# H41R60.net
KiCad netlist of a schematic drawn in EAGLE
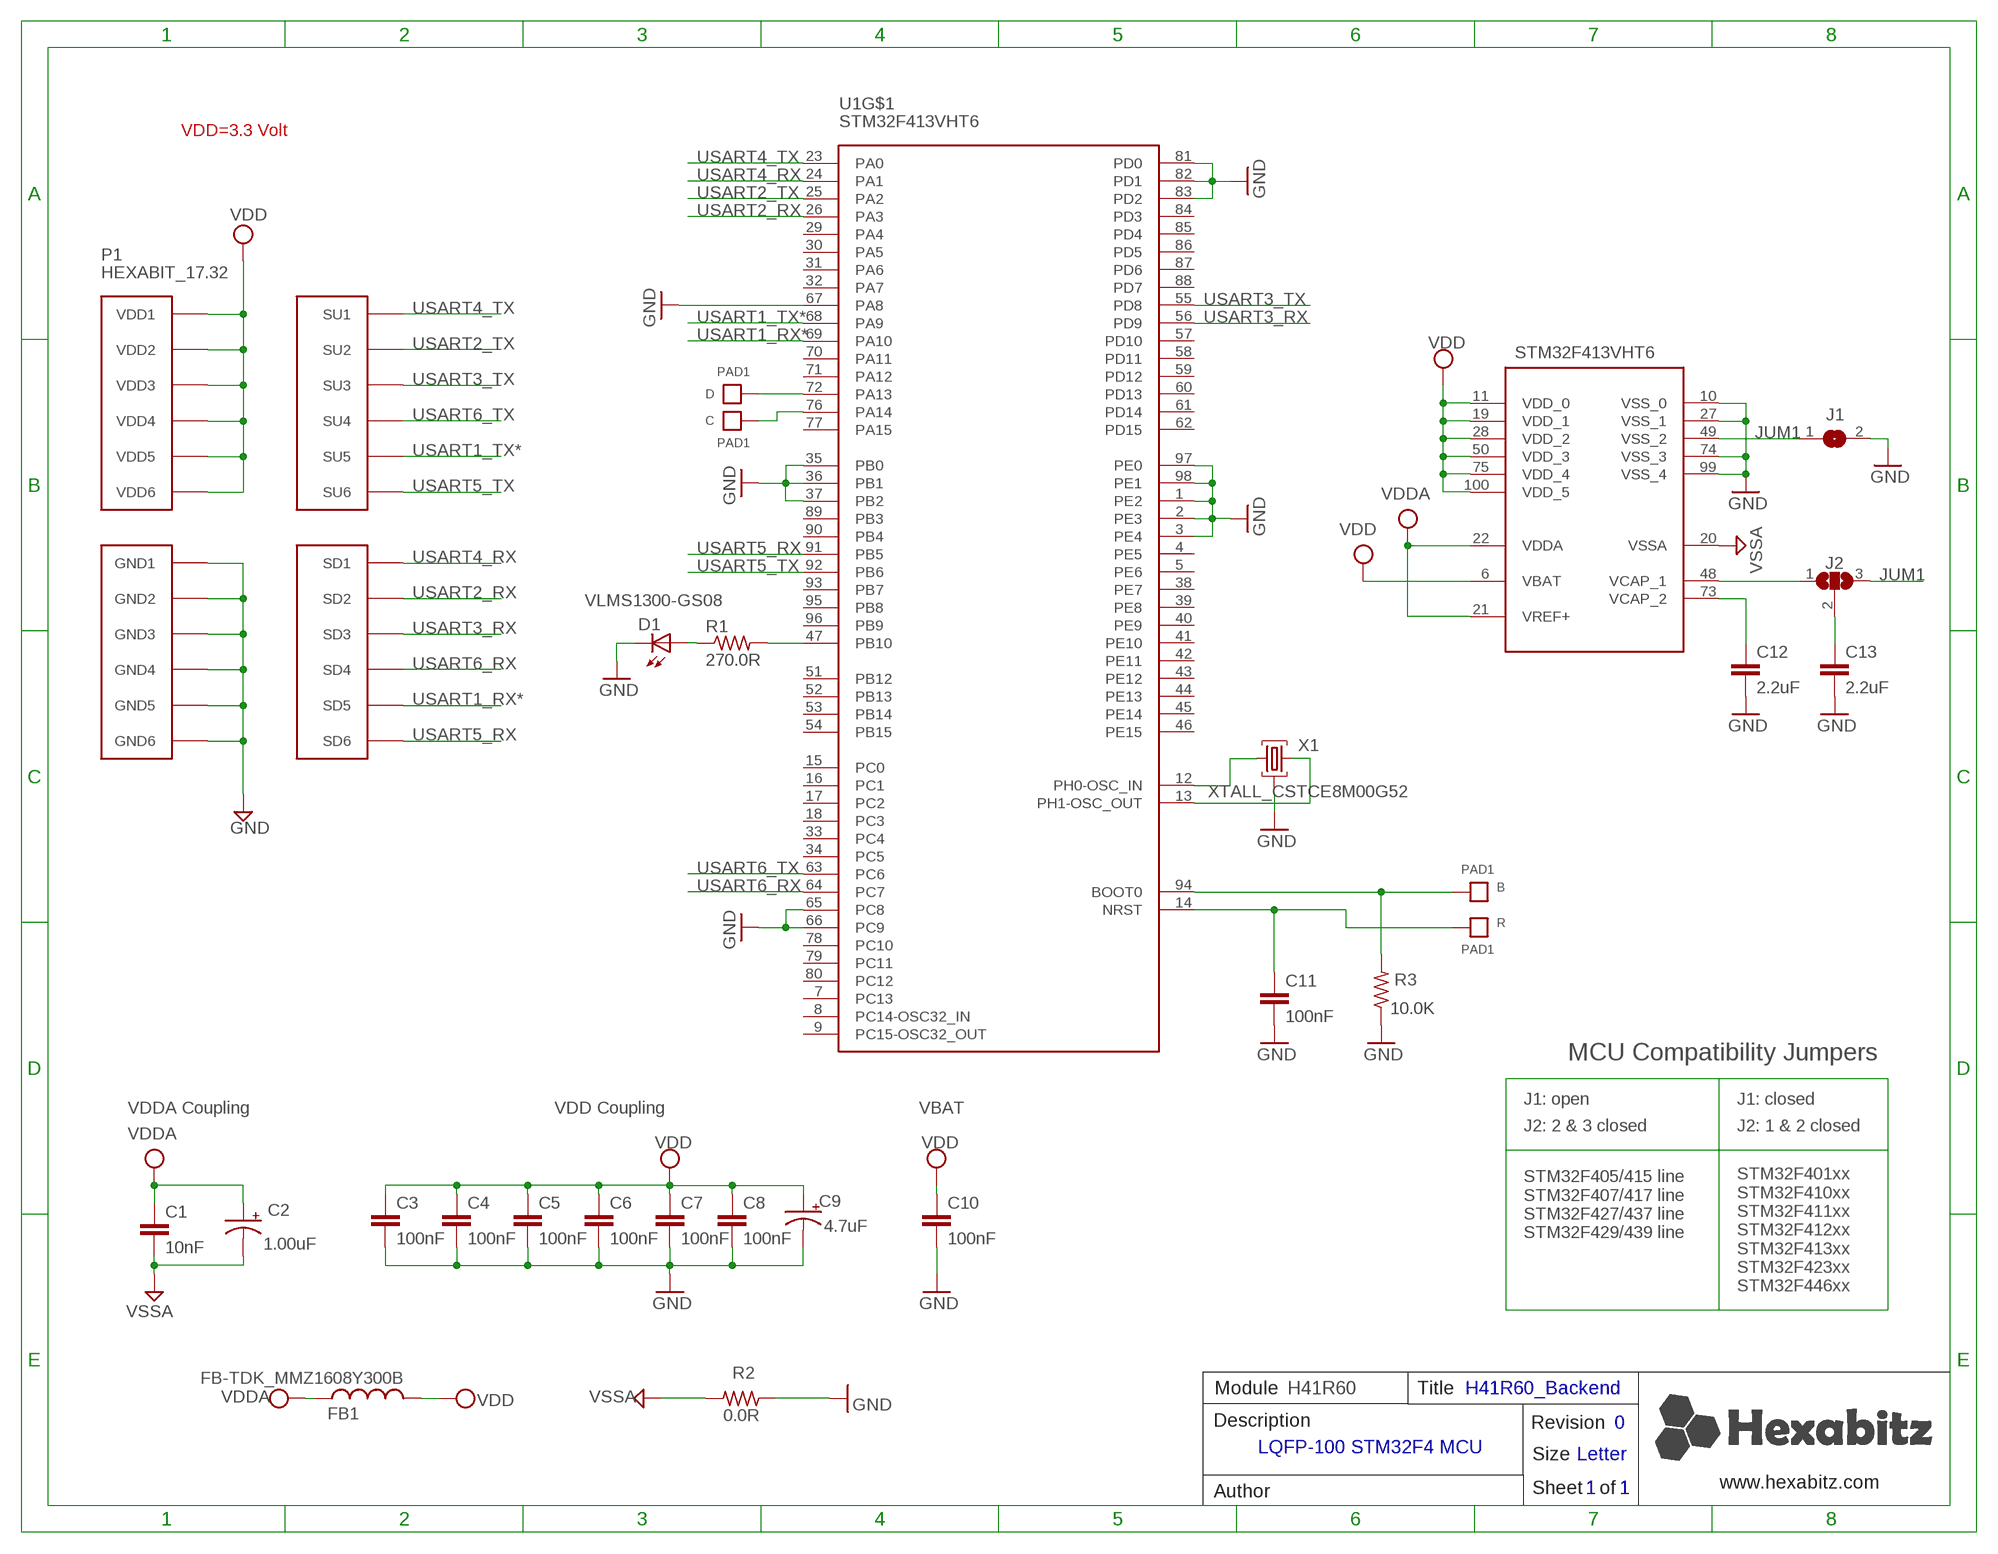
[diagram p0: schematic, sheet 1]

(export (version "E")
  (design (tool "Eeschema 10.0.6"))
  (components
    (comp (ref "B")
      (value "PAD1")
      (footprint "eagle-import:PAD1")
      (libsource (lib "eagle-import") (part "PAD1"))
    )
    (comp (ref "C")
      (value "PAD1")
      (footprint "eagle-import:PAD1")
      (libsource (lib "eagle-import") (part "PAD1"))
    )
    (comp (ref "C1")
      (value "10nF")
      (footprint "eagle-import:C-0603")
      (fields
        (field (name "CAPACITANCE") "10nF")
        (field (name "MFN") "KEMET")
        (field (name "MPN") "C0603C103K5RACTU")
        (field (name "OCTOPART_URL") "https://octopart.com/c0603c103k5ractu-kemet-133094?r=sp&s=R_iPBxLnSmGqhkU2rIMFpg")
        (field (name "TOLERANCE") "10%")
        (field (name "VOLTAGE_RATING") "50V")
      )
      (libsource (lib "eagle-import") (part "C-0603"))
    )
    (comp (ref "C2")
      (value "1.00uF")
      (footprint "eagle-import:C-0805-POL")
      (fields
        (field (name "CAPACITANCE") "1.00uF")
        (field (name "MFN") "Yageo")
        (field (name "MPN") "CC0805KKX7R7BB105")
        (field (name "OCTOPART_URL") "https://octopart.com/cc0805kkx7r7bb105-yageo-8376555?r=sp&s=YKl1wwtkROau_X5nniH2ig")
        (field (name "TOLERANCE") "10%")
        (field (name "VOLTAGE_RATING") "16V")
      )
      (libsource (lib "eagle-import") (part "C-0805-POL"))
    )
    (comp (ref "C3")
      (value "100nF")
      (footprint "eagle-import:C-0603")
      (fields
        (field (name "CAPACITANCE") "100nF")
        (field (name "MFN") "KEMET")
        (field (name "MPN") "C0603C104K8RACTU")
        (field (name "OCTOPART_URL") "https://octopart.com/c0603c104k8ractu-kemet-145075?r=sp&s=9bS9ASSwSEqMCE9KBEQZ0g")
        (field (name "TOLERANCE") "10%")
        (field (name "VOLTAGE_RATING") "10V")
      )
      (libsource (lib "eagle-import") (part "C-0603"))
    )
    (comp (ref "C4")
      (value "100nF")
      (footprint "eagle-import:C-0603")
      (fields
        (field (name "CAPACITANCE") "100nF")
        (field (name "MFN") "KEMET")
        (field (name "MPN") "C0603C104K8RACTU")
        (field (name "OCTOPART_URL") "https://octopart.com/c0603c104k8ractu-kemet-145075?r=sp&s=9bS9ASSwSEqMCE9KBEQZ0g")
        (field (name "TOLERANCE") "10%")
        (field (name "VOLTAGE_RATING") "10V")
      )
      (libsource (lib "eagle-import") (part "C-0603"))
    )
    (comp (ref "C5")
      (value "100nF")
      (footprint "eagle-import:C-0603")
      (fields
        (field (name "CAPACITANCE") "100nF")
        (field (name "MFN") "KEMET")
        (field (name "MPN") "C0603C104K8RACTU")
        (field (name "OCTOPART_URL") "https://octopart.com/c0603c104k8ractu-kemet-145075?r=sp&s=9bS9ASSwSEqMCE9KBEQZ0g")
        (field (name "TOLERANCE") "10%")
        (field (name "VOLTAGE_RATING") "10V")
      )
      (libsource (lib "eagle-import") (part "C-0603"))
    )
    (comp (ref "C6")
      (value "100nF")
      (footprint "eagle-import:C-0603")
      (fields
        (field (name "CAPACITANCE") "100nF")
        (field (name "MFN") "KEMET")
        (field (name "MPN") "C0603C104K8RACTU")
        (field (name "OCTOPART_URL") "https://octopart.com/c0603c104k8ractu-kemet-145075?r=sp&s=9bS9ASSwSEqMCE9KBEQZ0g")
        (field (name "TOLERANCE") "10%")
        (field (name "VOLTAGE_RATING") "10V")
      )
      (libsource (lib "eagle-import") (part "C-0603"))
    )
    (comp (ref "C7")
      (value "100nF")
      (footprint "eagle-import:C-0603")
      (fields
        (field (name "CAPACITANCE") "100nF")
        (field (name "MFN") "KEMET")
        (field (name "MPN") "C0603C104K8RACTU")
        (field (name "OCTOPART_URL") "https://octopart.com/c0603c104k8ractu-kemet-145075?r=sp&s=9bS9ASSwSEqMCE9KBEQZ0g")
        (field (name "TOLERANCE") "10%")
        (field (name "VOLTAGE_RATING") "10")
      )
      (libsource (lib "eagle-import") (part "C-0603"))
    )
    (comp (ref "C8")
      (value "100nF")
      (footprint "eagle-import:C-0603")
      (fields
        (field (name "CAPACITANCE") "100nF")
        (field (name "MFN") "KEMET")
        (field (name "MPN") "C0603C104K8RACTU")
        (field (name "OCTOPART_URL") "https://octopart.com/c0603c104k8ractu-kemet-145075?r=sp&s=9bS9ASSwSEqMCE9KBEQZ0g")
        (field (name "TOLERANCE") "10%")
        (field (name "VOLTAGE_RATING") "10V")
      )
      (libsource (lib "eagle-import") (part "C-0603"))
    )
    (comp (ref "C9")
      (value "4.7uF")
      (footprint "eagle-import:C-0805-POL")
      (fields
        (field (name "CAPACITANCE") "4.7uF")
        (field (name "MFN") "Murata")
        (field (name "MPN") "GRM21BC81E475KA12L")
        (field (name "OCTOPART_URL") "https://octopart.com/grm21bc81e475ka12l-murata-10331911?r=sp&s=RY3qZSD8T6mG6TC9CHI5qQ")
        (field (name "TOLERANCE") "10%")
        (field (name "VOLTAGE_RATING") "25V")
      )
      (libsource (lib "eagle-import") (part "C-0805-POL"))
    )
    (comp (ref "C10")
      (value "100nF")
      (footprint "eagle-import:C-0603")
      (fields
        (field (name "CAPACITANCE") "100nF")
        (field (name "MFN") "KEMET")
        (field (name "MPN") "C0603C104K8RACTU")
        (field (name "OCTOPART_URL") "https://octopart.com/c0603c104k8ractu-kemet-145075?r=sp&s=9bS9ASSwSEqMCE9KBEQZ0g")
        (field (name "TOLERANCE") "10V")
        (field (name "VOLTAGE_RATING") "10%")
      )
      (libsource (lib "eagle-import") (part "C-0603"))
    )
    (comp (ref "C11")
      (value "100nF")
      (footprint "eagle-import:C-0603")
      (fields
        (field (name "CAPACITANCE") "100nF")
        (field (name "MFN") "KEMET")
        (field (name "MPN") "C0603C104K8RACTU")
        (field (name "OCTOPART_URL") "https://octopart.com/c0603c104k8ractu-kemet-145075?r=sp&s=9bS9ASSwSEqMCE9KBEQZ0g")
        (field (name "TOLERANCE") "10%")
        (field (name "VOLTAGE_RATING") "10V")
      )
      (libsource (lib "eagle-import") (part "C-0603"))
    )
    (comp (ref "C12")
      (value "2.2uF")
      (footprint "eagle-import:C-0603")
      (fields
        (field (name "CAPACITANCE") "2.2uF")
        (field (name "MFN") "TDK Corporation")
        (field (name "MPN") "C1608X5R1C225K080AB")
        (field (name "OCTOPART_URL") "https://octopart.com/c1608x5r1c225k080ab-tdk-26013481?r=sp&s=zh0P7eqWSJSPxGSwstsLZg")
        (field (name "TOLERANCE") "16V")
        (field (name "VOLTAGE_RATING") "20%")
      )
      (libsource (lib "eagle-import") (part "C-0603"))
    )
    (comp (ref "C13")
      (value "2.2uF")
      (footprint "eagle-import:C-0603")
      (fields
        (field (name "CAPACITANCE") "2.2uF")
        (field (name "MFN") "TDK Corporation")
        (field (name "MPN") "C1608X5R1C225K080AB")
        (field (name "OCTOPART_URL") "https://octopart.com/c1608x5r1c225k080ab-tdk-26013481?r=sp&s=zh0P7eqWSJSPxGSwstsLZg")
        (field (name "TOLERANCE") "16V")
        (field (name "VOLTAGE_RATING") "20%")
      )
      (libsource (lib "eagle-import") (part "C-0603"))
    )
    (comp (ref "D")
      (value "PAD1")
      (footprint "eagle-import:PAD1")
      (libsource (lib "eagle-import") (part "PAD1"))
    )
    (comp (ref "D1")
      (value "VLMS1300-GS08")
      (footprint "eagle-import:VLMS1300-GS08")
      (fields
        (field (name "MFN") "Vishay")
        (field (name "MPN") "VLMS1300-GS08")
        (field (name "OCTOPART_URL") "https://octopart.com/vlms1300-gs08-vishay-21709201?r=sp&s=_gcP4_q8T1SC6PJQPTQ9yA")
      )
      (libsource (lib "eagle-import") (part "VLMS1300-GS08"))
    )
    (comp (ref "FB1")
      (value "FB-TDK_MMZ1608Y300B")
      (footprint "eagle-import:FB-TDK_MMZ1608Y300B")
      (fields
        (field (name "MFN") "TDK ")
        (field (name "MPN") "MMZ1608Y300B")
        (field (name "OCTOPART_URL") "https://octopart.com/mmz1608y300b-tdk-368280?r=sp&s=cd9_2ZEqQ9q9UNBuQgHAiA")
      )
      (libsource (lib "eagle-import") (part "FB-TDK_MMZ1608Y300B"))
    )
    (comp (ref "J1") (value "SJ") (footprint "eagle-import:SJ") (libsource (lib "eagle-import") (part "SJ")))
    (comp (ref "J2")
      (value "SJ2W")
      (footprint "eagle-import:SJ_2")
      (libsource (lib "eagle-import") (part "SJ2W"))
    )
    (comp (ref "P1")
      (value "HEXABIT_17.32")
      (footprint "eagle-import:HEXABIT_17.32")
      (libsource (lib "eagle-import") (part "HEXABIT_?17.32"))
    )
    (comp (ref "R")
      (value "PAD1")
      (footprint "eagle-import:PAD1")
      (libsource (lib "eagle-import") (part "PAD1"))
    )
    (comp (ref "R1")
      (value "270.0R")
      (footprint "eagle-import:R-0603")
      (fields
        (field (name "MFN") "Yageo")
        (field (name "MPN") "RC0603FR-07270RL")
        (field (name "OCTOPART_URL") "https://octopart.com/search?q=RC0603FR-07270RL&start=0")
        (field (name "RESISTANCE") "270.0 Ohm")
        (field (name "TOLERANCE") "1%")
      )
      (libsource (lib "eagle-import") (part "R-0603"))
    )
    (comp (ref "R2")
      (value "0.0R")
      (footprint "eagle-import:R-0603")
      (fields
        (field (name "MFN") "Yageo")
        (field (name "MPN") "RC0603JR-070RL")
        (field (name "OCTOPART_URL") "https://octopart.com/rc0603jr-070rl-yageo-1241539?r=sp&s=X2NteqRjRNWrnx42Y0aliA")
        (field (name "RESISTANCE") "0.0 Ohm")
      )
      (libsource (lib "eagle-import") (part "R-0603"))
    )
    (comp (ref "R3")
      (value "10.0K")
      (footprint "eagle-import:R-0603")
      (fields
        (field (name "MFN") "Yageo")
        (field (name "MPN") "RC0603JR-0710KL")
        (field (name "OCTOPART_URL") "https://octopart.com/search?q=RC0603JR-0710KL&start=0")
        (field (name "RESISTANCE") "10.0K Ohm")
        (field (name "TOLERANCE") "5%")
      )
      (libsource (lib "eagle-import") (part "R-0603"))
    )
    (comp (ref "U1")
      (value "STM32F413VHT6")
      (footprint "eagle-import:LQFP-100")
      (libsource (lib "eagle-import") (part "STM32F413VHT6"))
    )
    (comp (ref "X1")
      (value "XTALL_CSTCE8M00G52")
      (footprint "eagle-import:XTALL_CSTCE8M00G52")
      (fields (field (name "MPN") "CSTCE8M00G52Z-R0"))
      (libsource (lib "eagle-import") (part "XTALL_CSTCE8M00G52"))
    )
  )
  (nets
    (net (code "1") (name "/JUM1") (class "Default")
      (node (ref "J1") (pin "1") (pinfunction "1_1") (pintype "passive"))
      (node (ref "J2") (pin "3") (pinfunction "3_3") (pintype "passive"))
      (node (ref "U1") (pin "49") (pinfunction "VSS_2_49") (pintype "power_in"))
    )
    (net (code "3") (name "/USART1_RX*") (class "Default")
      (node (ref "P1") (pin "PAD_PD5") (pinfunction "SD5_PAD_PD5") (pintype "bidirectional"))
      (node (ref "U1") (pin "69") (pinfunction "PA10_69") (pintype "bidirectional"))
    )
    (net (code "4") (name "/USART1_TX*") (class "Default")
      (node (ref "P1") (pin "PAD_PU5") (pinfunction "SU5_PAD_PU5") (pintype "bidirectional"))
      (node (ref "U1") (pin "68") (pinfunction "PA9_68") (pintype "bidirectional"))
    )
    (net (code "5") (name "/USART2_RX") (class "Default")
      (node (ref "P1") (pin "PAD_PD2") (pinfunction "SD2_PAD_PD2") (pintype "bidirectional"))
      (node (ref "U1") (pin "26") (pinfunction "PA3_26") (pintype "bidirectional"))
    )
    (net (code "6") (name "/USART2_TX") (class "Default")
      (node (ref "P1") (pin "PAD_PU2") (pinfunction "SU2_PAD_PU2") (pintype "bidirectional"))
      (node (ref "U1") (pin "25") (pinfunction "PA2_25") (pintype "bidirectional"))
    )
    (net (code "7") (name "/USART3_RX") (class "Default")
      (node (ref "P1") (pin "PAD_PD3") (pinfunction "SD3_PAD_PD3") (pintype "bidirectional"))
      (node (ref "U1") (pin "56") (pinfunction "PD9_56") (pintype "bidirectional"))
    )
    (net (code "8") (name "/USART3_TX") (class "Default")
      (node (ref "P1") (pin "PAD_PU3") (pinfunction "SU3_PAD_PU3") (pintype "bidirectional"))
      (node (ref "U1") (pin "55") (pinfunction "PD8_55") (pintype "bidirectional"))
    )
    (net (code "9") (name "/USART4_RX") (class "Default")
      (node (ref "P1") (pin "PAD_PD1") (pinfunction "SD1_PAD_PD1") (pintype "bidirectional"))
      (node (ref "U1") (pin "24") (pinfunction "PA1_24") (pintype "bidirectional"))
    )
    (net (code "10") (name "/USART4_TX") (class "Default")
      (node (ref "P1") (pin "PAD_PU1") (pinfunction "SU1_PAD_PU1") (pintype "bidirectional"))
      (node (ref "U1") (pin "23") (pinfunction "PA0_23") (pintype "bidirectional"))
    )
    (net (code "11") (name "/USART5_RX") (class "Default")
      (node (ref "P1") (pin "PAD_PD6") (pinfunction "SD6_PAD_PD6") (pintype "bidirectional"))
      (node (ref "U1") (pin "91") (pinfunction "PB5_91") (pintype "bidirectional"))
    )
    (net (code "12") (name "/USART5_TX") (class "Default")
      (node (ref "P1") (pin "PAD_PU6") (pinfunction "SU6_PAD_PU6") (pintype "bidirectional"))
      (node (ref "U1") (pin "92") (pinfunction "PB6_92") (pintype "bidirectional"))
    )
    (net (code "13") (name "/USART6_RX") (class "Default")
      (node (ref "P1") (pin "PAD_PD4") (pinfunction "SD4_PAD_PD4") (pintype "bidirectional"))
      (node (ref "U1") (pin "64") (pinfunction "PC7_64") (pintype "bidirectional"))
    )
    (net (code "14") (name "/USART6_TX") (class "Default")
      (node (ref "P1") (pin "PAD_PU4") (pinfunction "SU4_PAD_PU4") (pintype "bidirectional"))
      (node (ref "U1") (pin "63") (pinfunction "PC6_63") (pintype "bidirectional"))
    )
    (net (code "15") (name "GND") (class "Default")
      (node (ref "C10") (pin "2") (pinfunction "2_2") (pintype "passive"))
      (node (ref "C11") (pin "2") (pinfunction "2_2") (pintype "passive"))
      (node (ref "C12") (pin "2") (pinfunction "2_2") (pintype "passive"))
      (node (ref "C13") (pin "2") (pinfunction "2_2") (pintype "passive"))
      (node (ref "C3") (pin "2") (pinfunction "2_2") (pintype "passive"))
      (node (ref "C4") (pin "2") (pinfunction "2_2") (pintype "passive"))
      (node (ref "C5") (pin "2") (pinfunction "2_2") (pintype "passive"))
      (node (ref "C6") (pin "2") (pinfunction "2_2") (pintype "passive"))
      (node (ref "C7") (pin "2") (pinfunction "2_2") (pintype "passive"))
      (node (ref "C8") (pin "2") (pinfunction "2_2") (pintype "passive"))
      (node (ref "C9") (pin "2") (pinfunction "-_2") (pintype "passive"))
      (node (ref "D1") (pin "C") (pinfunction "C_C") (pintype "passive"))
      (node (ref "J1") (pin "2") (pinfunction "2_2") (pintype "passive"))
      (node (ref "P1") (pin "PAD_PD10") (pinfunction "GND4_PAD_PD10") (pintype "power_in"))
      (node (ref "P1") (pin "PAD_PD11") (pinfunction "GND5_PAD_PD11") (pintype "power_in"))
      (node (ref "P1") (pin "PAD_PD12") (pinfunction "GND6_PAD_PD12") (pintype "power_in"))
      (node (ref "P1") (pin "PAD_PD7") (pinfunction "GND1_PAD_PD7") (pintype "power_in"))
      (node (ref "P1") (pin "PAD_PD8") (pinfunction "GND2_PAD_PD8") (pintype "power_in"))
      (node (ref "P1") (pin "PAD_PD9") (pinfunction "GND3_PAD_PD9") (pintype "power_in"))
      (node (ref "R2") (pin "1") (pinfunction "1_1") (pintype "passive"))
      (node (ref "R3") (pin "1") (pinfunction "1_1") (pintype "passive"))
      (node (ref "U1") (pin "1") (pinfunction "PE2_1") (pintype "bidirectional"))
      (node (ref "U1") (pin "10") (pinfunction "VSS_0_10") (pintype "power_in"))
      (node (ref "U1") (pin "2") (pinfunction "PE3_2") (pintype "bidirectional"))
      (node (ref "U1") (pin "27") (pinfunction "VSS_1_27") (pintype "power_in"))
      (node (ref "U1") (pin "3") (pinfunction "PE4_3") (pintype "bidirectional"))
      (node (ref "U1") (pin "35") (pinfunction "PB0_35") (pintype "bidirectional"))
      (node (ref "U1") (pin "36") (pinfunction "PB1_36") (pintype "bidirectional"))
      (node (ref "U1") (pin "37") (pinfunction "PB2_37") (pintype "bidirectional"))
      (node (ref "U1") (pin "65") (pinfunction "PC8_65") (pintype "bidirectional"))
      (node (ref "U1") (pin "66") (pinfunction "PC9_66") (pintype "bidirectional"))
      (node (ref "U1") (pin "67") (pinfunction "PA8_67") (pintype "bidirectional"))
      (node (ref "U1") (pin "74") (pinfunction "VSS_3_74") (pintype "power_in"))
      (node (ref "U1") (pin "81") (pinfunction "PD0_81") (pintype "bidirectional"))
      (node (ref "U1") (pin "82") (pinfunction "PD1_82") (pintype "bidirectional"))
      (node (ref "U1") (pin "83") (pinfunction "PD2_83") (pintype "bidirectional"))
      (node (ref "U1") (pin "97") (pinfunction "PE0_97") (pintype "bidirectional"))
      (node (ref "U1") (pin "98") (pinfunction "PE1_98") (pintype "bidirectional"))
      (node (ref "U1") (pin "99") (pinfunction "VSS_4_99") (pintype "power_in"))
      (node (ref "X1") (pin "P$2") (pinfunction "2_P$2") (pintype "passive"))
    )
    (net (code "16") (name "Net-(C13-Pad1)") (class "Default")
      (node (ref "C13") (pin "1") (pinfunction "1_1") (pintype "passive"))
      (node (ref "J2") (pin "2") (pinfunction "2_2") (pintype "passive"))
    )
    (net (code "17") (name "Net-(D1-PadA)") (class "Default")
      (node (ref "D1") (pin "A") (pinfunction "A_A") (pintype "passive"))
      (node (ref "R1") (pin "1") (pinfunction "1_1") (pintype "passive"))
    )
    (net (code "18") (name "Net-(U1A-BOOT0)") (class "Default")
      (node (ref "B") (pin "P$1") (pinfunction "P$1_P$1") (pintype "passive"))
      (node (ref "B") (pin "P$2") (pinfunction "P$1_P$2") (pintype "passive"))
      (node (ref "R3") (pin "2") (pinfunction "2_2") (pintype "passive"))
      (node (ref "U1") (pin "94") (pinfunction "BOOT0_94") (pintype "input"))
    )
    (net (code "19") (name "Net-(U1A-NRST)") (class "Default")
      (node (ref "C11") (pin "1") (pinfunction "1_1") (pintype "passive"))
      (node (ref "R") (pin "P$1") (pinfunction "P$1_P$1") (pintype "passive"))
      (node (ref "R") (pin "P$2") (pinfunction "P$1_P$2") (pintype "passive"))
      (node (ref "U1") (pin "14") (pinfunction "NRST_14") (pintype "passive"))
    )
    (net (code "20") (name "Net-(U1A-PA13)") (class "Default")
      (node (ref "D") (pin "P$1") (pinfunction "P$1_P$1") (pintype "passive"))
      (node (ref "D") (pin "P$2") (pinfunction "P$1_P$2") (pintype "passive"))
      (node (ref "U1") (pin "72") (pinfunction "PA13_72") (pintype "bidirectional"))
    )
    (net (code "21") (name "Net-(U1A-PA14)") (class "Default")
      (node (ref "C") (pin "P$1") (pinfunction "P$1_P$1") (pintype "passive"))
      (node (ref "C") (pin "P$2") (pinfunction "P$1_P$2") (pintype "passive"))
      (node (ref "U1") (pin "76") (pinfunction "PA14_76") (pintype "bidirectional"))
    )
    (net (code "22") (name "Net-(U1A-PB10)") (class "Default")
      (node (ref "R1") (pin "2") (pinfunction "2_2") (pintype "passive"))
      (node (ref "U1") (pin "47") (pinfunction "PB10_47") (pintype "bidirectional"))
    )
    (net (code "23") (name "Net-(U1A-PH0-OSC_IN)") (class "Default")
      (node (ref "U1") (pin "12") (pinfunction "PH0-OSC_IN_12") (pintype "bidirectional"))
      (node (ref "X1") (pin "P$1") (pinfunction "1_P$1") (pintype "passive"))
    )
    (net (code "24") (name "Net-(U1A-PH1-OSC_OUT)") (class "Default")
      (node (ref "U1") (pin "13") (pinfunction "PH1-OSC_OUT_13") (pintype "bidirectional"))
      (node (ref "X1") (pin "P$3") (pinfunction "3_P$3") (pintype "passive"))
    )
    (net (code "25") (name "Net-(U1B-VCAP_1)") (class "Default")
      (node (ref "J2") (pin "1") (pinfunction "1_1") (pintype "passive"))
      (node (ref "U1") (pin "48") (pinfunction "VCAP_1_48") (pintype "power_in"))
    )
    (net (code "26") (name "Net-(U1B-VCAP_2)") (class "Default")
      (node (ref "C12") (pin "1") (pinfunction "1_1") (pintype "passive"))
      (node (ref "U1") (pin "73") (pinfunction "VCAP_2_73") (pintype "power_in"))
    )
    (net (code "27") (name "VDD") (class "Default")
      (node (ref "C10") (pin "1") (pinfunction "1_1") (pintype "passive"))
      (node (ref "C3") (pin "1") (pinfunction "1_1") (pintype "passive"))
      (node (ref "C4") (pin "1") (pinfunction "1_1") (pintype "passive"))
      (node (ref "C5") (pin "1") (pinfunction "1_1") (pintype "passive"))
      (node (ref "C6") (pin "1") (pinfunction "1_1") (pintype "passive"))
      (node (ref "C7") (pin "1") (pinfunction "1_1") (pintype "passive"))
      (node (ref "C8") (pin "1") (pinfunction "1_1") (pintype "passive"))
      (node (ref "C9") (pin "1") (pinfunction "+_1") (pintype "passive"))
      (node (ref "FB1") (pin "2") (pinfunction "2_2") (pintype "passive"))
      (node (ref "P1") (pin "PAD_PU10") (pinfunction "VDD4_PAD_PU10") (pintype "power_in"))
      (node (ref "P1") (pin "PAD_PU11") (pinfunction "VDD5_PAD_PU11") (pintype "power_in"))
      (node (ref "P1") (pin "PAD_PU12") (pinfunction "VDD6_PAD_PU12") (pintype "power_in"))
      (node (ref "P1") (pin "PAD_PU7") (pinfunction "VDD1_PAD_PU7") (pintype "power_in"))
      (node (ref "P1") (pin "PAD_PU8") (pinfunction "VDD2_PAD_PU8") (pintype "power_in"))
      (node (ref "P1") (pin "PAD_PU9") (pinfunction "VDD3_PAD_PU9") (pintype "power_in"))
      (node (ref "U1") (pin "100") (pinfunction "VDD_5_100") (pintype "power_in"))
      (node (ref "U1") (pin "11") (pinfunction "VDD_0_11") (pintype "power_in"))
      (node (ref "U1") (pin "19") (pinfunction "VDD_1_19") (pintype "power_in"))
      (node (ref "U1") (pin "28") (pinfunction "VDD_2_28") (pintype "power_in"))
      (node (ref "U1") (pin "50") (pinfunction "VDD_3_50") (pintype "power_in"))
      (node (ref "U1") (pin "6") (pinfunction "VBAT_6") (pintype "power_in"))
      (node (ref "U1") (pin "75") (pinfunction "VDD_4_75") (pintype "power_in"))
    )
    (net (code "28") (name "VDDA") (class "Default")
      (node (ref "C1") (pin "1") (pinfunction "1_1") (pintype "passive"))
      (node (ref "C2") (pin "1") (pinfunction "+_1") (pintype "passive"))
      (node (ref "FB1") (pin "1") (pinfunction "1_1") (pintype "passive"))
      (node (ref "U1") (pin "21") (pinfunction "VREF+_21") (pintype "power_in"))
      (node (ref "U1") (pin "22") (pinfunction "VDDA_22") (pintype "power_in"))
    )
    (net (code "29") (name "VSSA") (class "Default")
      (node (ref "C1") (pin "2") (pinfunction "2_2") (pintype "passive"))
      (node (ref "C2") (pin "2") (pinfunction "-_2") (pintype "passive"))
      (node (ref "R2") (pin "2") (pinfunction "2_2") (pintype "passive"))
      (node (ref "U1") (pin "20") (pinfunction "VSSA_20") (pintype "power_in"))
    )
    (net (code "30") (name "unconnected-(U1A-PA4-Pad29)") (class "Default")
      (node (ref "U1") (pin "29") (pinfunction "PA4_29") (pintype "bidirectional"))
    )
    (net (code "31") (name "unconnected-(U1A-PA5-Pad30)") (class "Default")
      (node (ref "U1") (pin "30") (pinfunction "PA5_30") (pintype "bidirectional"))
    )
    (net (code "32") (name "unconnected-(U1A-PA6-Pad31)") (class "Default")
      (node (ref "U1") (pin "31") (pinfunction "PA6_31") (pintype "bidirectional"))
    )
    (net (code "33") (name "unconnected-(U1A-PA7-Pad32)") (class "Default")
      (node (ref "U1") (pin "32") (pinfunction "PA7_32") (pintype "bidirectional"))
    )
    (net (code "34") (name "unconnected-(U1A-PA11-Pad70)") (class "Default")
      (node (ref "U1") (pin "70") (pinfunction "PA11_70") (pintype "bidirectional"))
    )
    (net (code "35") (name "unconnected-(U1A-PA12-Pad71)") (class "Default")
      (node (ref "U1") (pin "71") (pinfunction "PA12_71") (pintype "bidirectional"))
    )
    (net (code "36") (name "unconnected-(U1A-PA15-Pad77)") (class "Default")
      (node (ref "U1") (pin "77") (pinfunction "PA15_77") (pintype "bidirectional"))
    )
    (net (code "37") (name "unconnected-(U1A-PB3-Pad89)") (class "Default")
      (node (ref "U1") (pin "89") (pinfunction "PB3_89") (pintype "bidirectional"))
    )
    (net (code "38") (name "unconnected-(U1A-PB4-Pad90)") (class "Default")
      (node (ref "U1") (pin "90") (pinfunction "PB4_90") (pintype "bidirectional"))
    )
    (net (code "39") (name "unconnected-(U1A-PB7-Pad93)") (class "Default")
      (node (ref "U1") (pin "93") (pinfunction "PB7_93") (pintype "bidirectional"))
    )
    (net (code "40") (name "unconnected-(U1A-PB8-Pad95)") (class "Default")
      (node (ref "U1") (pin "95") (pinfunction "PB8_95") (pintype "bidirectional"))
    )
    (net (code "41") (name "unconnected-(U1A-PB9-Pad96)") (class "Default")
      (node (ref "U1") (pin "96") (pinfunction "PB9_96") (pintype "bidirectional"))
    )
    (net (code "42") (name "unconnected-(U1A-PB12-Pad51)") (class "Default")
      (node (ref "U1") (pin "51") (pinfunction "PB12_51") (pintype "bidirectional"))
    )
    (net (code "43") (name "unconnected-(U1A-PB13-Pad52)") (class "Default")
      (node (ref "U1") (pin "52") (pinfunction "PB13_52") (pintype "bidirectional"))
    )
    (net (code "44") (name "unconnected-(U1A-PB14-Pad53)") (class "Default")
      (node (ref "U1") (pin "53") (pinfunction "PB14_53") (pintype "bidirectional"))
    )
    (net (code "45") (name "unconnected-(U1A-PB15-Pad54)") (class "Default")
      (node (ref "U1") (pin "54") (pinfunction "PB15_54") (pintype "bidirectional"))
    )
    (net (code "46") (name "unconnected-(U1A-PC0-Pad15)") (class "Default")
      (node (ref "U1") (pin "15") (pinfunction "PC0_15") (pintype "bidirectional"))
    )
    (net (code "47") (name "unconnected-(U1A-PC1-Pad16)") (class "Default")
      (node (ref "U1") (pin "16") (pinfunction "PC1_16") (pintype "bidirectional"))
    )
    (net (code "48") (name "unconnected-(U1A-PC2-Pad17)") (class "Default")
      (node (ref "U1") (pin "17") (pinfunction "PC2_17") (pintype "bidirectional"))
    )
    (net (code "49") (name "unconnected-(U1A-PC3-Pad18)") (class "Default")
      (node (ref "U1") (pin "18") (pinfunction "PC3_18") (pintype "bidirectional"))
    )
    (net (code "50") (name "unconnected-(U1A-PC4-Pad33)") (class "Default")
      (node (ref "U1") (pin "33") (pinfunction "PC4_33") (pintype "bidirectional"))
    )
    (net (code "51") (name "unconnected-(U1A-PC5-Pad34)") (class "Default")
      (node (ref "U1") (pin "34") (pinfunction "PC5_34") (pintype "bidirectional"))
    )
    (net (code "52") (name "unconnected-(U1A-PC10-Pad78)") (class "Default")
      (node (ref "U1") (pin "78") (pinfunction "PC10_78") (pintype "bidirectional"))
    )
    (net (code "53") (name "unconnected-(U1A-PC11-Pad79)") (class "Default")
      (node (ref "U1") (pin "79") (pinfunction "PC11_79") (pintype "bidirectional"))
    )
    (net (code "54") (name "unconnected-(U1A-PC12-Pad80)") (class "Default")
      (node (ref "U1") (pin "80") (pinfunction "PC12_80") (pintype "bidirectional"))
    )
    (net (code "55") (name "unconnected-(U1A-PC13-Pad7)") (class "Default")
      (node (ref "U1") (pin "7") (pinfunction "PC13_7") (pintype "bidirectional"))
    )
    (net (code "56") (name "unconnected-(U1A-PC14-OSC32_IN-Pad8)") (class "Default")
      (node (ref "U1") (pin "8") (pinfunction "PC14-OSC32_IN_8") (pintype "bidirectional"))
    )
    (net (code "57") (name "unconnected-(U1A-PC15-OSC32_OUT-Pad9)") (class "Default")
      (node (ref "U1") (pin "9") (pinfunction "PC15-OSC32_OUT_9") (pintype "bidirectional"))
    )
    (net (code "58") (name "unconnected-(U1A-PD3-Pad84)") (class "Default")
      (node (ref "U1") (pin "84") (pinfunction "PD3_84") (pintype "bidirectional"))
    )
    (net (code "59") (name "unconnected-(U1A-PD4-Pad85)") (class "Default")
      (node (ref "U1") (pin "85") (pinfunction "PD4_85") (pintype "bidirectional"))
    )
    (net (code "60") (name "unconnected-(U1A-PD5-Pad86)") (class "Default")
      (node (ref "U1") (pin "86") (pinfunction "PD5_86") (pintype "bidirectional"))
    )
    (net (code "61") (name "unconnected-(U1A-PD6-Pad87)") (class "Default")
      (node (ref "U1") (pin "87") (pinfunction "PD6_87") (pintype "bidirectional"))
    )
    (net (code "62") (name "unconnected-(U1A-PD7-Pad88)") (class "Default")
      (node (ref "U1") (pin "88") (pinfunction "PD7_88") (pintype "bidirectional"))
    )
    (net (code "63") (name "unconnected-(U1A-PD10-Pad57)") (class "Default")
      (node (ref "U1") (pin "57") (pinfunction "PD10_57") (pintype "bidirectional"))
    )
    (net (code "64") (name "unconnected-(U1A-PD11-Pad58)") (class "Default")
      (node (ref "U1") (pin "58") (pinfunction "PD11_58") (pintype "bidirectional"))
    )
    (net (code "65") (name "unconnected-(U1A-PD12-Pad59)") (class "Default")
      (node (ref "U1") (pin "59") (pinfunction "PD12_59") (pintype "bidirectional"))
    )
    (net (code "66") (name "unconnected-(U1A-PD13-Pad60)") (class "Default")
      (node (ref "U1") (pin "60") (pinfunction "PD13_60") (pintype "bidirectional"))
    )
    (net (code "67") (name "unconnected-(U1A-PD14-Pad61)") (class "Default")
      (node (ref "U1") (pin "61") (pinfunction "PD14_61") (pintype "bidirectional"))
    )
    (net (code "68") (name "unconnected-(U1A-PD15-Pad62)") (class "Default")
      (node (ref "U1") (pin "62") (pinfunction "PD15_62") (pintype "bidirectional"))
    )
    (net (code "69") (name "unconnected-(U1A-PE5-Pad4)") (class "Default")
      (node (ref "U1") (pin "4") (pinfunction "PE5_4") (pintype "bidirectional"))
    )
    (net (code "70") (name "unconnected-(U1A-PE6-Pad5)") (class "Default")
      (node (ref "U1") (pin "5") (pinfunction "PE6_5") (pintype "bidirectional"))
    )
    (net (code "71") (name "unconnected-(U1A-PE7-Pad38)") (class "Default")
      (node (ref "U1") (pin "38") (pinfunction "PE7_38") (pintype "bidirectional"))
    )
    (net (code "72") (name "unconnected-(U1A-PE8-Pad39)") (class "Default")
      (node (ref "U1") (pin "39") (pinfunction "PE8_39") (pintype "bidirectional"))
    )
    (net (code "73") (name "unconnected-(U1A-PE9-Pad40)") (class "Default")
      (node (ref "U1") (pin "40") (pinfunction "PE9_40") (pintype "bidirectional"))
    )
    (net (code "74") (name "unconnected-(U1A-PE10-Pad41)") (class "Default")
      (node (ref "U1") (pin "41") (pinfunction "PE10_41") (pintype "bidirectional"))
    )
    (net (code "75") (name "unconnected-(U1A-PE11-Pad42)") (class "Default")
      (node (ref "U1") (pin "42") (pinfunction "PE11_42") (pintype "bidirectional"))
    )
    (net (code "76") (name "unconnected-(U1A-PE12-Pad43)") (class "Default")
      (node (ref "U1") (pin "43") (pinfunction "PE12_43") (pintype "bidirectional"))
    )
    (net (code "77") (name "unconnected-(U1A-PE13-Pad44)") (class "Default")
      (node (ref "U1") (pin "44") (pinfunction "PE13_44") (pintype "bidirectional"))
    )
    (net (code "78") (name "unconnected-(U1A-PE14-Pad45)") (class "Default")
      (node (ref "U1") (pin "45") (pinfunction "PE14_45") (pintype "bidirectional"))
    )
    (net (code "79") (name "unconnected-(U1A-PE15-Pad46)") (class "Default")
      (node (ref "U1") (pin "46") (pinfunction "PE15_46") (pintype "bidirectional"))
    )
  )
)
